# Sheet1.net
KiCad netlist of a schematic drawn in Altium Designer
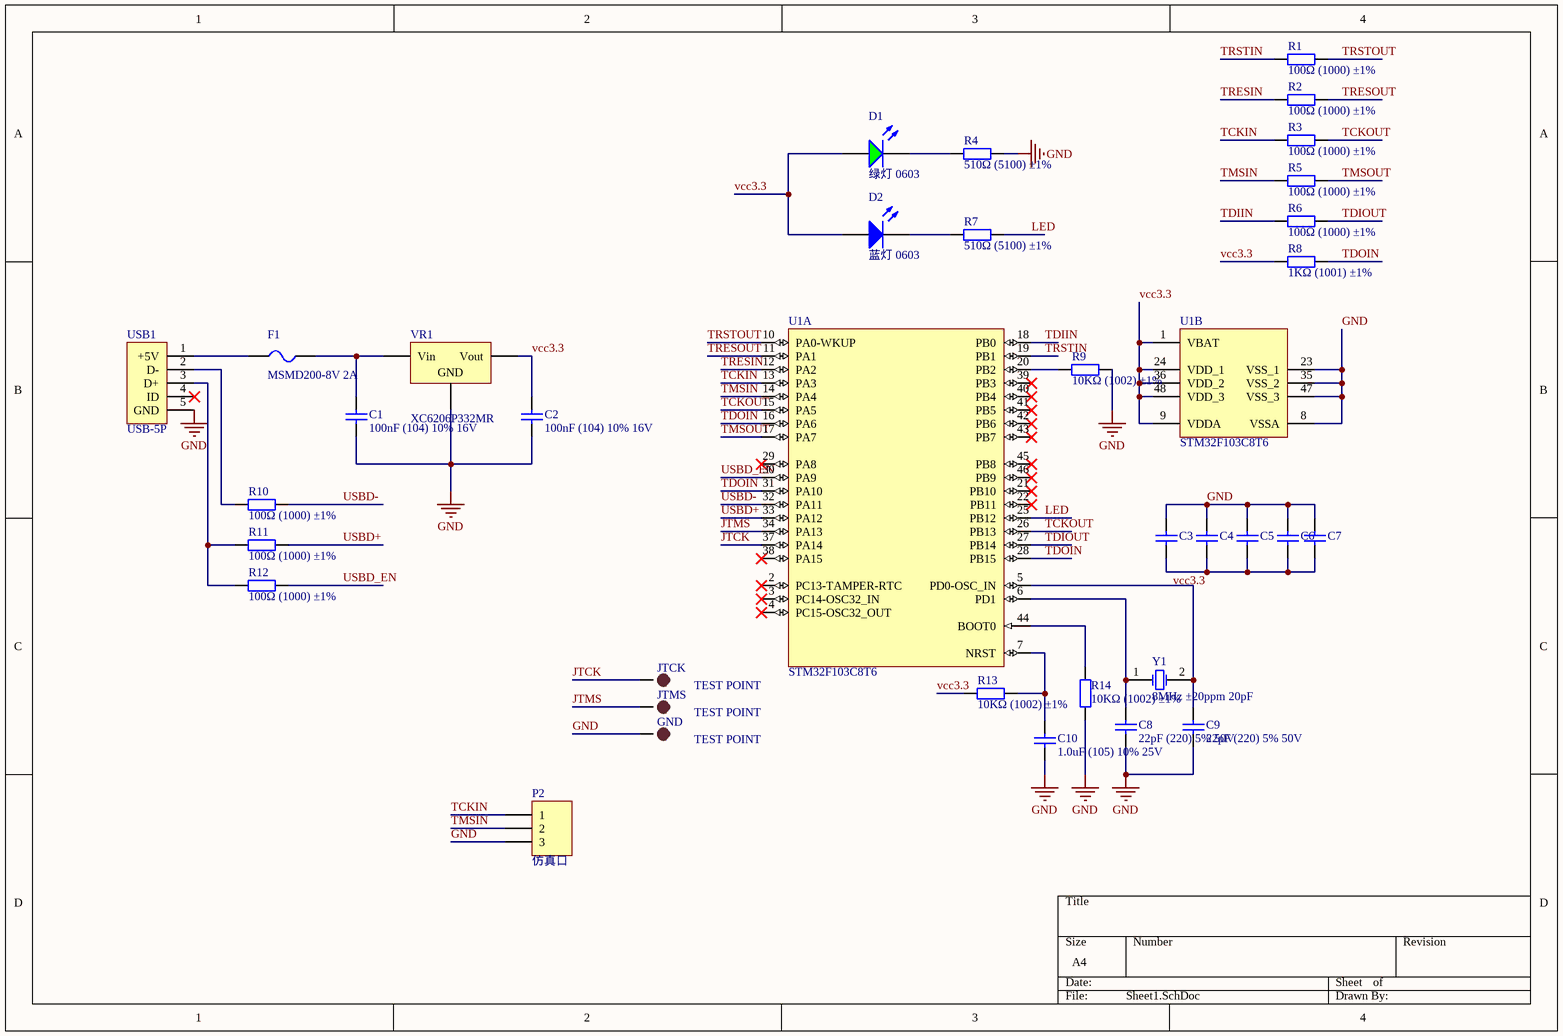
[diagram p0: Sheet1.SchDoc]

(export (version "E")
  (design (tool "Eeschema 10.0.6"))
  (components
    (comp (ref "C1")
      (value "100nF (104) 10% 16V")
      (footprint "0402_C")
      (description "贴片电容")
      (libsource (lib "ROSLIB") (part "0402 100nF (104) 10% 16V"))
    )
    (comp (ref "C2")
      (value "100nF (104) 10% 16V")
      (footprint "0402_C")
      (description "贴片电容")
      (libsource (lib "ROSLIB") (part "0402 100nF (104) 10% 16V"))
    )
    (comp (ref "C3")
      (value "100nF (104) 10% 16V")
      (footprint "0402_C")
      (description "贴片电容")
      (libsource (lib "Miscellaneous Devices LC") (part "0402 100nF (104) 10% 16V"))
    )
    (comp (ref "C4")
      (value "100nF (104) 10% 16V")
      (footprint "0402_C")
      (description "贴片电容")
      (libsource (lib "Miscellaneous Devices LC") (part "0402 100nF (104) 10% 16V"))
    )
    (comp (ref "C5")
      (value "100nF (104) 10% 16V")
      (footprint "0402_C")
      (description "贴片电容")
      (libsource (lib "Miscellaneous Devices LC") (part "0402 100nF (104) 10% 16V"))
    )
    (comp (ref "C6")
      (value "100nF (104) 10% 16V")
      (footprint "0402_C")
      (description "贴片电容")
      (libsource (lib "Miscellaneous Devices LC") (part "0402 100nF (104) 10% 16V"))
    )
    (comp (ref "C7")
      (value "100nF (104) 10% 16V")
      (footprint "0402_C")
      (description "贴片电容")
      (libsource (lib "Miscellaneous Devices LC") (part "0402 100nF (104) 10% 16V"))
    )
    (comp (ref "C8")
      (value "22pF (220) 5% 50V")
      (footprint "0402_C")
      (description "贴片电容")
      (libsource (lib "ROSLIB") (part "0402 22pF (220) 5% 50V"))
    )
    (comp (ref "C9")
      (value "22pF (220) 5% 50V")
      (footprint "0402_C")
      (description "贴片电容")
      (libsource (lib "ROSLIB") (part "0402 22pF (220) 5% 50V"))
    )
    (comp (ref "C10")
      (value "1.0uF (105) 10% 25V")
      (footprint "0402_C")
      (description "贴片电容")
      (libsource (lib "Miscellaneous Devices LC") (part "0402 1.0uF (105) 10% 25V"))
    )
    (comp (ref "D1")
      (value "绿灯 0603")
      (footprint "0603_LED_S1")
      (description "发光二极管")
      (libsource (lib "Miscellaneous Devices LC") (part "0603 绿灯"))
    )
    (comp (ref "D2")
      (value "蓝灯 0603")
      (footprint "0603_LED_S1")
      (description "发光二极管")
      (libsource (lib "Miscellaneous Devices LC") (part "0603 蓝灯"))
    )
    (comp (ref "F1")
      (value "MSMD200-8V 2A")
      (footprint "FU 0805")
      (description "贴片保险丝")
      (fields (field (name "版权归属") "源创客"))
      (libsource (lib "ROSLIB") (part "FU"))
    )
    (comp (ref "GND")
      (value "TEST POINT")
      (footprint "TP-1.5")
      (description "测试点")
      (libsource (lib "B2B_Integrated_Library") (part "TEST-POINT"))
    )
    (comp (ref "JTCK")
      (value "TEST POINT")
      (footprint "TP-1.5")
      (description "测试点")
      (libsource (lib "B2B_Integrated_Library") (part "TEST-POINT"))
    )
    (comp (ref "JTMS")
      (value "TEST POINT")
      (footprint "TP-1.5")
      (description "测试点")
      (libsource (lib "B2B_Integrated_Library") (part "TEST-POINT"))
    )
    (comp (ref "P2")
      (value "仿真口")
      (footprint "HDR1X3")
      (description "Header, 3-Pin")
      (fields (field (name "PUBLISHER") "Altium Limited"))
      (libsource (lib "Miscellaneous Connectors") (part "Header 3"))
    )
    (comp (ref "R1")
      (value "100Ω (1000) ±1%")
      (footprint "0402_R")
      (description "贴片电阻")
      (libsource (lib "Miscellaneous Devices LC") (part "0402 100Ω (1000) 1%"))
    )
    (comp (ref "R2")
      (value "100Ω (1000) ±1%")
      (footprint "0402_R")
      (description "贴片电阻")
      (libsource (lib "Miscellaneous Devices LC") (part "0402 100Ω (1000) 1%"))
    )
    (comp (ref "R3")
      (value "100Ω (1000) ±1%")
      (footprint "0402_R")
      (description "贴片电阻")
      (libsource (lib "Miscellaneous Devices LC") (part "0402 100Ω (1000) 1%"))
    )
    (comp (ref "R4")
      (value "510Ω (5100) ±1%")
      (footprint "0603_R")
      (description "贴片电阻")
      (libsource (lib "Miscellaneous Devices LC") (part "0603 510Ω (5100) 1%"))
    )
    (comp (ref "R5")
      (value "100Ω (1000) ±1%")
      (footprint "0402_R")
      (description "贴片电阻")
      (libsource (lib "Miscellaneous Devices LC") (part "0402 100Ω (1000) 1%"))
    )
    (comp (ref "R6")
      (value "100Ω (1000) ±1%")
      (footprint "0402_R")
      (description "贴片电阻")
      (libsource (lib "Miscellaneous Devices LC") (part "0402 100Ω (1000) 1%"))
    )
    (comp (ref "R7")
      (value "510Ω (5100) ±1%")
      (footprint "0603_R")
      (description "贴片电阻")
      (libsource (lib "Miscellaneous Devices LC") (part "0603 510Ω (5100) 1%"))
    )
    (comp (ref "R8")
      (value "1KΩ (1001) ±1%")
      (footprint "0402_R")
      (description "贴片电阻")
      (libsource (lib "Miscellaneous Devices LC") (part "0402 1KΩ (1001) 1%"))
    )
    (comp (ref "R9")
      (value "10KΩ (1002) ±1%")
      (footprint "0402_R")
      (description "贴片电阻")
      (libsource (lib "Miscellaneous Devices LC") (part "0402 10KΩ (1002) 1%"))
    )
    (comp (ref "R10")
      (value "100Ω (1000) ±1%")
      (footprint "0402_R")
      (description "贴片电阻")
      (libsource (lib "Miscellaneous Devices LC") (part "0402 100Ω (1000) 1%"))
    )
    (comp (ref "R11")
      (value "100Ω (1000) ±1%")
      (footprint "0402_R")
      (description "贴片电阻")
      (libsource (lib "Miscellaneous Devices LC") (part "0402 100Ω (1000) 1%"))
    )
    (comp (ref "R12")
      (value "100Ω (1000) ±1%")
      (footprint "0402_R")
      (description "贴片电阻")
      (libsource (lib "Miscellaneous Devices LC") (part "0402 100Ω (1000) 1%"))
    )
    (comp (ref "R13")
      (value "10KΩ (1002) ±1%")
      (footprint "0402_R")
      (description "贴片电阻")
      (libsource (lib "Miscellaneous Devices LC") (part "0402 10KΩ (1002) 1%"))
    )
    (comp (ref "R14")
      (value "10KΩ (1002) ±1%")
      (footprint "0402_R")
      (description "贴片电阻")
      (libsource (lib "") (part "0402 10KΩ (1002) 1%_1"))
    )
    (comp (ref "U1")
      (value "STM32F103C8T6")
      (footprint "LQFP-48_7x7x05P")
      (description "ARM")
      (libsource (lib "Miscellaneous Devices LC") (part "STM32F103C8T6"))
    )
    (comp (ref "USB1")
      (value "USB-5P")
      (footprint "USB-MICRO_A")
      (description "微型USB母座")
      (fields (field (name "版权归属") "源创客"))
      (libsource (lib "ROSLIB") (part "USB-5P"))
    )
    (comp (ref "VR1")
      (value "XC6206P332MR")
      (footprint "SOT-23-3L")
      (description "低压差线性稳压(LDO)")
      (libsource (lib "Miscellaneous Devices LC") (part "SOT-23 XC6206P332MR"))
    )
    (comp (ref "Y1")
      (value "8MHz ±20ppm 20pF")
      (footprint "SMD-5032_2P")
      (description "贴片晶振")
      (libsource (lib "ROSLIB") (part "SMD-5032_2P 8MHz 20ppm 20pF"))
    )
  )
  (nets
    (net (code "1") (name "/JTCK") (class "Default")
      (node (ref "JTCK") (pin "1") (pinfunction "1_1") (pintype "passive"))
      (node (ref "U1") (pin "37") (pinfunction "PA14_37") (pintype "bidirectional"))
    )
    (net (code "2") (name "/JTMS") (class "Default")
      (node (ref "JTMS") (pin "1") (pinfunction "1_1") (pintype "passive"))
      (node (ref "U1") (pin "34") (pinfunction "PA13_34") (pintype "bidirectional"))
    )
    (net (code "3") (name "/LED") (class "Default")
      (node (ref "R7") (pin "2") (pinfunction "2_2") (pintype "passive"))
      (node (ref "U1") (pin "25") (pinfunction "PB12_25") (pintype "bidirectional"))
    )
    (net (code "4") (name "/TCKIN") (class "Default")
      (node (ref "P2") (pin "1") (pinfunction "1_1") (pintype "passive"))
      (node (ref "R3") (pin "1") (pinfunction "1_1") (pintype "passive"))
      (node (ref "U1") (pin "13") (pinfunction "PA3_13") (pintype "bidirectional"))
    )
    (net (code "5") (name "/TCKOUT") (class "Default")
      (node (ref "R3") (pin "2") (pinfunction "2_2") (pintype "passive"))
      (node (ref "U1") (pin "15") (pinfunction "PA5_15") (pintype "bidirectional"))
      (node (ref "U1") (pin "26") (pinfunction "PB13_26") (pintype "bidirectional"))
    )
    (net (code "6") (name "/TDIIN") (class "Default")
      (node (ref "R6") (pin "1") (pinfunction "1_1") (pintype "passive"))
      (node (ref "U1") (pin "18") (pinfunction "PB0_18") (pintype "bidirectional"))
    )
    (net (code "7") (name "/TDIOUT") (class "Default")
      (node (ref "R6") (pin "2") (pinfunction "2_2") (pintype "passive"))
      (node (ref "U1") (pin "27") (pinfunction "PB14_27") (pintype "bidirectional"))
    )
    (net (code "8") (name "/TDOIN") (class "Default")
      (node (ref "R8") (pin "2") (pinfunction "2_2") (pintype "passive"))
      (node (ref "U1") (pin "16") (pinfunction "PA6_16") (pintype "bidirectional"))
      (node (ref "U1") (pin "28") (pinfunction "PB15_28") (pintype "bidirectional"))
      (node (ref "U1") (pin "31") (pinfunction "PA10_31") (pintype "bidirectional"))
    )
    (net (code "9") (name "/TMSIN") (class "Default")
      (node (ref "P2") (pin "2") (pinfunction "2_2") (pintype "passive"))
      (node (ref "R5") (pin "1") (pinfunction "1_1") (pintype "passive"))
      (node (ref "U1") (pin "14") (pinfunction "PA4_14") (pintype "bidirectional"))
    )
    (net (code "10") (name "/TMSOUT") (class "Default")
      (node (ref "R5") (pin "2") (pinfunction "2_2") (pintype "passive"))
      (node (ref "U1") (pin "17") (pinfunction "PA7_17") (pintype "bidirectional"))
    )
    (net (code "11") (name "/TRESIN") (class "Default")
      (node (ref "R2") (pin "1") (pinfunction "1_1") (pintype "passive"))
      (node (ref "U1") (pin "12") (pinfunction "PA2_12") (pintype "bidirectional"))
    )
    (net (code "12") (name "/TRESOUT") (class "Default")
      (node (ref "R2") (pin "2") (pinfunction "2_2") (pintype "passive"))
      (node (ref "U1") (pin "11") (pinfunction "PA1_11") (pintype "bidirectional"))
    )
    (net (code "13") (name "/TRSTIN") (class "Default")
      (node (ref "R1") (pin "1") (pinfunction "1_1") (pintype "passive"))
      (node (ref "U1") (pin "19") (pinfunction "PB1_19") (pintype "bidirectional"))
    )
    (net (code "14") (name "/TRSTOUT") (class "Default")
      (node (ref "R1") (pin "2") (pinfunction "2_2") (pintype "passive"))
      (node (ref "U1") (pin "10") (pinfunction "PA0-WKUP_10") (pintype "bidirectional"))
    )
    (net (code "15") (name "/USBD+") (class "Default")
      (node (ref "R11") (pin "2") (pinfunction "2_2") (pintype "passive"))
      (node (ref "U1") (pin "33") (pinfunction "PA12_33") (pintype "bidirectional"))
    )
    (net (code "16") (name "/USBD-") (class "Default")
      (node (ref "R10") (pin "2") (pinfunction "2_2") (pintype "passive"))
      (node (ref "U1") (pin "32") (pinfunction "PA11_32") (pintype "bidirectional"))
    )
    (net (code "17") (name "/USBD_EN") (class "Default")
      (node (ref "R12") (pin "2") (pinfunction "2_2") (pintype "passive"))
      (node (ref "U1") (pin "30") (pinfunction "PA9_30") (pintype "bidirectional"))
    )
    (net (code "18") (name "/vcc3.3") (class "Default")
      (node (ref "C2") (pin "2") (pinfunction "2_2") (pintype "passive"))
      (node (ref "C3") (pin "1") (pinfunction "1_1") (pintype "passive"))
      (node (ref "C4") (pin "1") (pinfunction "1_1") (pintype "passive"))
      (node (ref "C5") (pin "1") (pinfunction "1_1") (pintype "passive"))
      (node (ref "C6") (pin "1") (pinfunction "1_1") (pintype "passive"))
      (node (ref "C7") (pin "1") (pinfunction "1_1") (pintype "passive"))
      (node (ref "D1") (pin "A") (pinfunction "A_A") (pintype "passive"))
      (node (ref "D2") (pin "A") (pinfunction "A_A") (pintype "passive"))
      (node (ref "R13") (pin "1") (pinfunction "1_1") (pintype "passive"))
      (node (ref "R8") (pin "1") (pinfunction "1_1") (pintype "passive"))
      (node (ref "U1") (pin "1") (pinfunction "VBAT_1") (pintype "power_in"))
      (node (ref "U1") (pin "24") (pinfunction "VDD_1_24") (pintype "power_in"))
      (node (ref "U1") (pin "36") (pinfunction "VDD_2_36") (pintype "power_in"))
      (node (ref "U1") (pin "48") (pinfunction "VDD_3_48") (pintype "power_in"))
      (node (ref "U1") (pin "9") (pinfunction "VDDA_9") (pintype "power_in"))
      (node (ref "VR1") (pin "2") (pinfunction "Vout_2") (pintype "passive"))
    )
    (net (code "19") (name "GND") (class "Default")
      (node (ref "C1") (pin "1") (pinfunction "1_1") (pintype "passive"))
      (node (ref "C10") (pin "1") (pinfunction "1_1") (pintype "passive"))
      (node (ref "C2") (pin "1") (pinfunction "1_1") (pintype "passive"))
      (node (ref "C3") (pin "2") (pinfunction "2_2") (pintype "passive"))
      (node (ref "C4") (pin "2") (pinfunction "2_2") (pintype "passive"))
      (node (ref "C5") (pin "2") (pinfunction "2_2") (pintype "passive"))
      (node (ref "C6") (pin "2") (pinfunction "2_2") (pintype "passive"))
      (node (ref "C7") (pin "2") (pinfunction "2_2") (pintype "passive"))
      (node (ref "C8") (pin "1") (pinfunction "1_1") (pintype "passive"))
      (node (ref "C9") (pin "1") (pinfunction "1_1") (pintype "passive"))
      (node (ref "GND") (pin "1") (pinfunction "1_1") (pintype "passive"))
      (node (ref "P2") (pin "3") (pinfunction "3_3") (pintype "passive"))
      (node (ref "R14") (pin "1") (pinfunction "1_1") (pintype "passive"))
      (node (ref "R4") (pin "2") (pinfunction "2_2") (pintype "passive"))
      (node (ref "R9") (pin "2") (pinfunction "2_2") (pintype "passive"))
      (node (ref "U1") (pin "23") (pinfunction "VSS_1_23") (pintype "power_in"))
      (node (ref "U1") (pin "35") (pinfunction "VSS_2_35") (pintype "power_in"))
      (node (ref "U1") (pin "47") (pinfunction "VSS_3_47") (pintype "power_in"))
      (node (ref "U1") (pin "8") (pinfunction "VSSA_8") (pintype "power_in"))
      (node (ref "USB1") (pin "5") (pinfunction "GND_5") (pintype "passive"))
      (node (ref "VR1") (pin "1") (pinfunction "GND_1") (pintype "passive"))
    )
    (net (code "20") (name "Net-(D1-PadK)") (class "Default")
      (node (ref "D1") (pin "K") (pinfunction "K_K") (pintype "passive"))
      (node (ref "R4") (pin "1") (pinfunction "1_1") (pintype "passive"))
    )
    (net (code "21") (name "Net-(D2-PadK)") (class "Default")
      (node (ref "D2") (pin "K") (pinfunction "K_K") (pintype "passive"))
      (node (ref "R7") (pin "1") (pinfunction "1_1") (pintype "passive"))
    )
    (net (code "22") (name "Net-(U1A-BOOT0)") (class "Default")
      (node (ref "R14") (pin "2") (pinfunction "2_2") (pintype "passive"))
      (node (ref "U1") (pin "44") (pinfunction "BOOT0_44") (pintype "input"))
    )
    (net (code "23") (name "Net-(U1A-NRST)") (class "Default")
      (node (ref "C10") (pin "2") (pinfunction "2_2") (pintype "passive"))
      (node (ref "R13") (pin "2") (pinfunction "2_2") (pintype "passive"))
      (node (ref "U1") (pin "7") (pinfunction "NRST_7") (pintype "bidirectional"))
    )
    (net (code "24") (name "Net-(U1A-PB2)") (class "Default")
      (node (ref "R9") (pin "1") (pinfunction "1_1") (pintype "passive"))
      (node (ref "U1") (pin "20") (pinfunction "PB2_20") (pintype "bidirectional"))
    )
    (net (code "25") (name "Net-(U1A-PD0-OSC_IN)") (class "Default")
      (node (ref "C9") (pin "2") (pinfunction "2_2") (pintype "passive"))
      (node (ref "U1") (pin "5") (pinfunction "PD0-OSC_IN_5") (pintype "bidirectional"))
      (node (ref "Y1") (pin "2") (pinfunction "OSC2_2") (pintype "passive"))
    )
    (net (code "26") (name "Net-(U1A-PD1)") (class "Default")
      (node (ref "C8") (pin "2") (pinfunction "2_2") (pintype "passive"))
      (node (ref "U1") (pin "6") (pinfunction "PD1_6") (pintype "bidirectional"))
      (node (ref "Y1") (pin "1") (pinfunction "OSC1_1") (pintype "passive"))
    )
    (net (code "27") (name "Net-(USB1-+5V)") (class "Default")
      (node (ref "F1") (pin "1") (pinfunction "1_1") (pintype "passive"))
      (node (ref "USB1") (pin "1") (pinfunction "+5V_1") (pintype "passive"))
    )
    (net (code "28") (name "Net-(USB1-D+)") (class "Default")
      (node (ref "R11") (pin "1") (pinfunction "1_1") (pintype "passive"))
      (node (ref "R12") (pin "1") (pinfunction "1_1") (pintype "passive"))
      (node (ref "USB1") (pin "3") (pinfunction "D+_3") (pintype "passive"))
    )
    (net (code "29") (name "Net-(USB1-D-)") (class "Default")
      (node (ref "R10") (pin "1") (pinfunction "1_1") (pintype "passive"))
      (node (ref "USB1") (pin "2") (pinfunction "D-_2") (pintype "passive"))
    )
    (net (code "30") (name "Net-(VR1-Vin)") (class "Default")
      (node (ref "C1") (pin "2") (pinfunction "2_2") (pintype "passive"))
      (node (ref "F1") (pin "2") (pinfunction "2_2") (pintype "passive"))
      (node (ref "VR1") (pin "3") (pinfunction "Vin_3") (pintype "passive"))
    )
    (net (code "31") (name "unconnected-(U1A-PA8-Pad29)") (class "Default")
      (node (ref "U1") (pin "29") (pinfunction "PA8_29") (pintype "bidirectional+no_connect"))
    )
    (net (code "32") (name "unconnected-(U1A-PA15-Pad38)") (class "Default")
      (node (ref "U1") (pin "38") (pinfunction "PA15_38") (pintype "bidirectional+no_connect"))
    )
    (net (code "33") (name "unconnected-(U1A-PB3-Pad39)") (class "Default")
      (node (ref "U1") (pin "39") (pinfunction "PB3_39") (pintype "bidirectional+no_connect"))
    )
    (net (code "34") (name "unconnected-(U1A-PB4-Pad40)") (class "Default")
      (node (ref "U1") (pin "40") (pinfunction "PB4_40") (pintype "bidirectional+no_connect"))
    )
    (net (code "35") (name "unconnected-(U1A-PB5-Pad41)") (class "Default")
      (node (ref "U1") (pin "41") (pinfunction "PB5_41") (pintype "bidirectional+no_connect"))
    )
    (net (code "36") (name "unconnected-(U1A-PB6-Pad42)") (class "Default")
      (node (ref "U1") (pin "42") (pinfunction "PB6_42") (pintype "bidirectional+no_connect"))
    )
    (net (code "37") (name "unconnected-(U1A-PB7-Pad43)") (class "Default")
      (node (ref "U1") (pin "43") (pinfunction "PB7_43") (pintype "bidirectional+no_connect"))
    )
    (net (code "38") (name "unconnected-(U1A-PB8-Pad45)") (class "Default")
      (node (ref "U1") (pin "45") (pinfunction "PB8_45") (pintype "bidirectional+no_connect"))
    )
    (net (code "39") (name "unconnected-(U1A-PB9-Pad46)") (class "Default")
      (node (ref "U1") (pin "46") (pinfunction "PB9_46") (pintype "bidirectional+no_connect"))
    )
    (net (code "40") (name "unconnected-(U1A-PB10-Pad21)") (class "Default")
      (node (ref "U1") (pin "21") (pinfunction "PB10_21") (pintype "bidirectional+no_connect"))
    )
    (net (code "41") (name "unconnected-(U1A-PB11-Pad22)") (class "Default")
      (node (ref "U1") (pin "22") (pinfunction "PB11_22") (pintype "bidirectional+no_connect"))
    )
    (net (code "42") (name "unconnected-(U1A-PC13-TAMPER-RTC-Pad2)") (class "Default")
      (node (ref "U1") (pin "2") (pinfunction "PC13-TAMPER-RTC_2") (pintype "bidirectional+no_connect"))
    )
    (net (code "43") (name "unconnected-(U1A-PC14-OSC32_IN-Pad3)") (class "Default")
      (node (ref "U1") (pin "3") (pinfunction "PC14-OSC32_IN_3") (pintype "bidirectional+no_connect"))
    )
    (net (code "44") (name "unconnected-(U1A-PC15-OSC32_OUT-Pad4)") (class "Default")
      (node (ref "U1") (pin "4") (pinfunction "PC15-OSC32_OUT_4") (pintype "bidirectional+no_connect"))
    )
    (net (code "45") (name "unconnected-(USB1-ID-Pad4)") (class "Default")
      (node (ref "USB1") (pin "4") (pinfunction "ID_4") (pintype "passive+no_connect"))
    )
  )
)
